# gsm2.net
KiCad netlist of a schematic drawn in Altium Designer
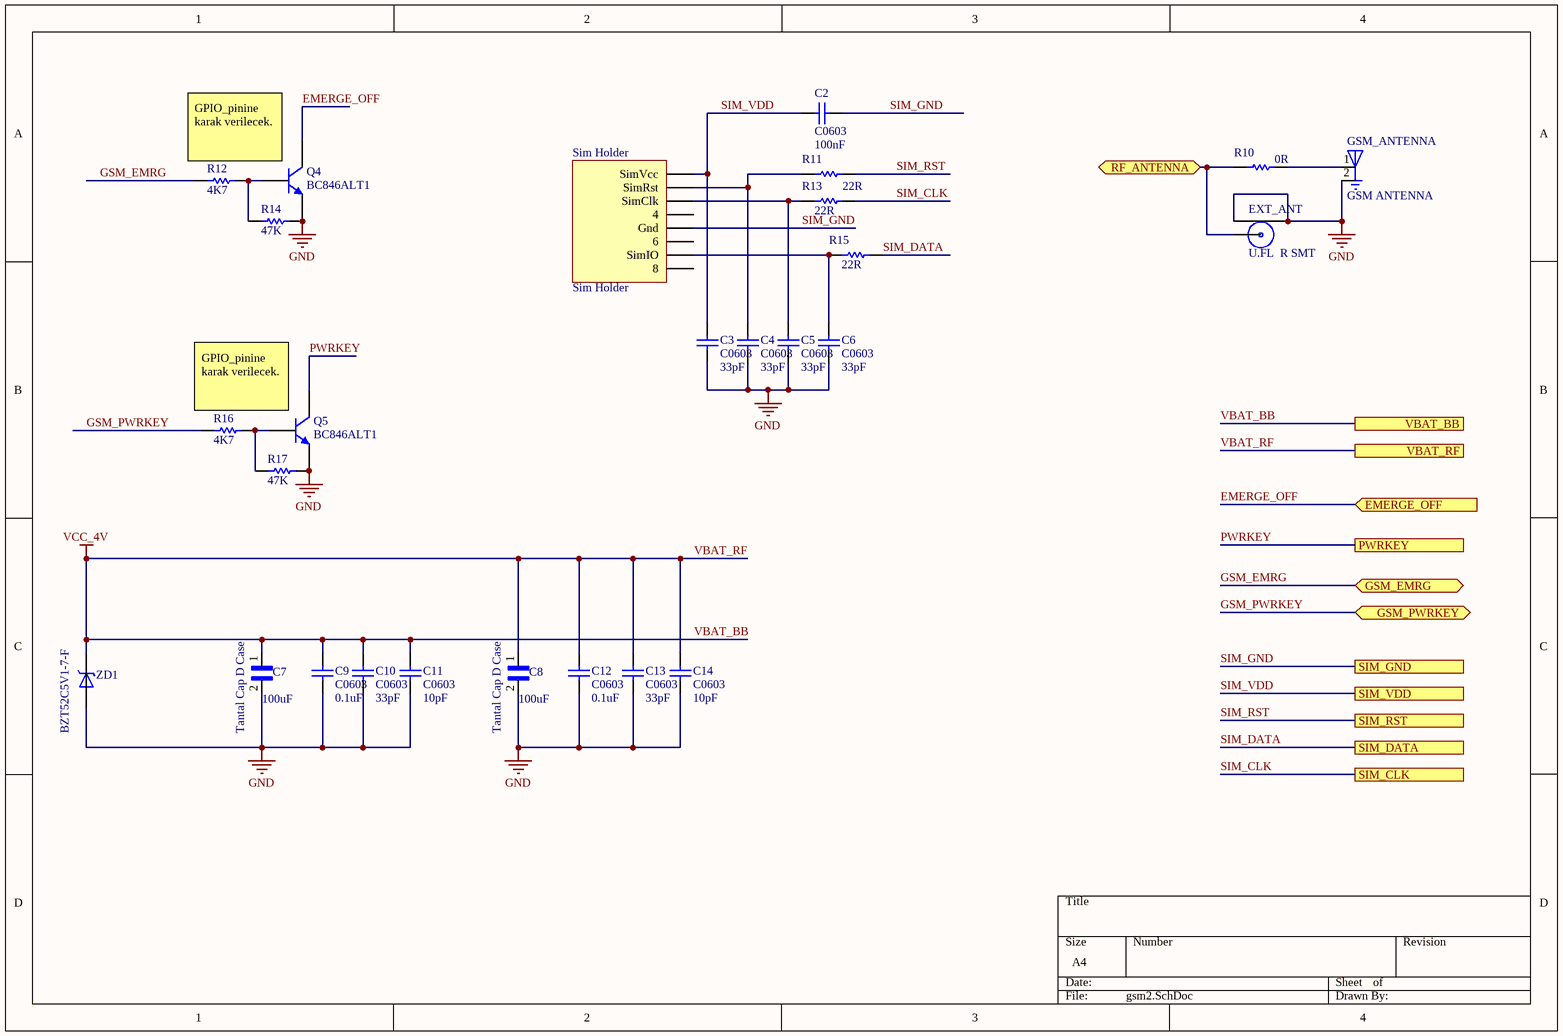
[diagram p0: gsm2.SchDoc]

(export (version "E")
  (design (tool "Eeschema 10.0.6"))
  (components
    (comp (ref "C2")
      (value "C0603")
      (footprint "C0603")
      (description "Ceramic Chip Capacitor - Standard")
      (fields (field (name "ALTIUM_VALUE") "100nF") (field (name "PUBLISHER") "Altium Limited"))
      (libsource (lib "haberlesme") (part "C0603"))
    )
    (comp (ref "C3")
      (value "C0603")
      (footprint "C0603")
      (description "Ceramic Chip Capacitor - Standard")
      (fields (field (name "ALTIUM_VALUE") "33pF") (field (name "PUBLISHER") "Altium Limited"))
      (libsource (lib "haberlesme") (part "C0603"))
    )
    (comp (ref "C4")
      (value "C0603")
      (footprint "C0603")
      (description "Ceramic Chip Capacitor - Standard")
      (fields (field (name "ALTIUM_VALUE") "33pF") (field (name "PUBLISHER") "Altium Limited"))
      (libsource (lib "haberlesme") (part "C0603"))
    )
    (comp (ref "C5")
      (value "C0603")
      (footprint "C0603")
      (description "Ceramic Chip Capacitor - Standard")
      (fields (field (name "ALTIUM_VALUE") "33pF") (field (name "PUBLISHER") "Altium Limited"))
      (libsource (lib "haberlesme") (part "C0603"))
    )
    (comp (ref "C6")
      (value "C0603")
      (footprint "C0603")
      (description "Ceramic Chip Capacitor - Standard")
      (fields (field (name "ALTIUM_VALUE") "33pF") (field (name "PUBLISHER") "Altium Limited"))
      (libsource (lib "haberlesme") (part "C0603"))
    )
    (comp (ref "C7")
      (value "Tantal Cap D Case")
      (footprint "Tantal Cap D Case")
      (fields (field (name "ALTIUM_VALUE") "100uF"))
      (libsource (lib "haberlesme") (part "Tantal Cap D Case"))
    )
    (comp (ref "C8")
      (value "Tantal Cap D Case")
      (footprint "Tantal Cap D Case")
      (fields (field (name "ALTIUM_VALUE") "100uF"))
      (libsource (lib "haberlesme") (part "Tantal Cap D Case"))
    )
    (comp (ref "C9")
      (value "C0603")
      (footprint "C0603")
      (description "Ceramic Chip Capacitor - Standard")
      (fields (field (name "ALTIUM_VALUE") "0.1uF") (field (name "PUBLISHER") "Altium Limited"))
      (libsource (lib "haberlesme") (part "C0603"))
    )
    (comp (ref "C10")
      (value "C0603")
      (footprint "C0603")
      (description "Ceramic Chip Capacitor - Standard")
      (fields (field (name "ALTIUM_VALUE") "33pF") (field (name "PUBLISHER") "Altium Limited"))
      (libsource (lib "haberlesme") (part "C0603"))
    )
    (comp (ref "C11")
      (value "C0603")
      (footprint "C0603")
      (description "Ceramic Chip Capacitor - Standard")
      (fields (field (name "ALTIUM_VALUE") "10pF") (field (name "PUBLISHER") "Altium Limited"))
      (libsource (lib "haberlesme") (part "C0603"))
    )
    (comp (ref "C12")
      (value "C0603")
      (footprint "C0603")
      (description "Ceramic Chip Capacitor - Standard")
      (fields (field (name "ALTIUM_VALUE") "0.1uF") (field (name "PUBLISHER") "Altium Limited"))
      (libsource (lib "haberlesme") (part "C0603"))
    )
    (comp (ref "C13")
      (value "C0603")
      (footprint "C0603")
      (description "Ceramic Chip Capacitor - Standard")
      (fields (field (name "ALTIUM_VALUE") "33pF") (field (name "PUBLISHER") "Altium Limited"))
      (libsource (lib "haberlesme") (part "C0603"))
    )
    (comp (ref "C14")
      (value "C0603")
      (footprint "C0603")
      (description "Ceramic Chip Capacitor - Standard")
      (fields (field (name "ALTIUM_VALUE") "10pF") (field (name "PUBLISHER") "Altium Limited"))
      (libsource (lib "haberlesme") (part "C0603"))
    )
    (comp (ref "EXT_ANT")
      (value "U.FL  R SMT")
      (footprint "U.FL  R SMT")
      (libsource (lib "haberlesme") (part "U.FL  R SMT"))
    )
    (comp (ref "GSM_ANTENNA")
      (value "GSM ANTENNA")
      (footprint "GSM ANTENNA")
      (libsource (lib "haberlesme") (part "GSM ANTENNA"))
    )
    (comp (ref "Q4")
      (value "BC846ALT1")
      (footprint "BC846")
      (description "General Purpose Transistor NPN Silicon")
      (fields (field (name "PUBLISHER") "Altium Limited"))
      (libsource (lib "Motorola Discrete BJT") (part "BC846ALT1"))
    )
    (comp (ref "Q5")
      (value "BC846ALT1")
      (footprint "BC846")
      (description "General Purpose Transistor NPN Silicon")
      (fields (field (name "PUBLISHER") "Altium Limited"))
      (libsource (lib "Motorola Discrete BJT") (part "BC846ALT1"))
    )
    (comp (ref "R10")
      (value "0R")
      (footprint "Isbak:CC1608-0603")
      (description "Resistor")
      (fields
        (field (name "MANUFACTURER") "Generic Components")
        (field (name "Comment") "Res0603")
        (field (name "PUBLISHER") "Altium Limited")
      )
      (libsource (lib "Isbak") (part "Res0603"))
    )
    (comp (ref "R11")
      (value "22R")
      (footprint "Isbak:CC1608-0603")
      (description "Resistor")
      (fields
        (field (name "MANUFACTURER") "Generic Components")
        (field (name "Comment") "Res0603")
        (field (name "PUBLISHER") "Altium Limited")
      )
      (libsource (lib "Isbak") (part "Res0603"))
    )
    (comp (ref "R12")
      (value "4K7")
      (footprint "Isbak:CC1608-0603")
      (description "Resistor")
      (fields
        (field (name "MANUFACTURER") "Generic Components")
        (field (name "Comment") "Res0603")
        (field (name "PUBLISHER") "Altium Limited")
      )
      (libsource (lib "Isbak") (part "Res0603"))
    )
    (comp (ref "R13")
      (value "22R")
      (footprint "Isbak:CC1608-0603")
      (description "Resistor")
      (fields
        (field (name "MANUFACTURER") "Generic Components")
        (field (name "Comment") "Res0603")
        (field (name "PUBLISHER") "Altium Limited")
      )
      (libsource (lib "Isbak") (part "Res0603"))
    )
    (comp (ref "R14")
      (value "47K")
      (footprint "Isbak:CC1608-0603")
      (description "Resistor")
      (fields
        (field (name "MANUFACTURER") "Generic Components")
        (field (name "Comment") "Res0603")
        (field (name "PUBLISHER") "Altium Limited")
      )
      (libsource (lib "Isbak") (part "Res0603"))
    )
    (comp (ref "R15")
      (value "22R")
      (footprint "Isbak:CC1608-0603")
      (description "Resistor")
      (fields
        (field (name "MANUFACTURER") "Generic Components")
        (field (name "Comment") "Res0603")
        (field (name "PUBLISHER") "Altium Limited")
      )
      (libsource (lib "Isbak") (part "Res0603"))
    )
    (comp (ref "R16")
      (value "4K7")
      (footprint "Isbak:CC1608-0603")
      (description "Resistor")
      (fields
        (field (name "MANUFACTURER") "Generic Components")
        (field (name "Comment") "Res0603")
        (field (name "PUBLISHER") "Altium Limited")
      )
      (libsource (lib "Isbak") (part "Res0603"))
    )
    (comp (ref "R17")
      (value "47K")
      (footprint "Isbak:CC1608-0603")
      (description "Resistor")
      (fields
        (field (name "MANUFACTURER") "Generic Components")
        (field (name "Comment") "Res0603")
        (field (name "PUBLISHER") "Altium Limited")
      )
      (libsource (lib "Isbak") (part "Res0603"))
    )
    (comp (ref "Sim Holder")
      (value "Sim Holder")
      (footprint "SIM HOLDER")
      (libsource (lib "haberlesme") (part "Sim Holder"))
    )
    (comp (ref "ZD1")
      (value "BZT52C5V1-7-F")
      (footprint "BZT52C5V1")
      (libsource (lib "haberlesme") (part "BZT52C5V1-7-F"))
    )
  )
  (nets
    (net (code "1") (name "/EMERGE_OFF") (class "Default")
      (node (ref "Q4") (pin "3") (pinfunction "C_3") (pintype "passive"))
    )
    (net (code "2") (name "/GSM_EMRG") (class "Default")
      (node (ref "R12") (pin "1") (pinfunction "1_1") (pintype "passive"))
    )
    (net (code "3") (name "/GSM_PWRKEY") (class "Default")
      (node (ref "R16") (pin "1") (pinfunction "1_1") (pintype "passive"))
    )
    (net (code "4") (name "/PWRKEY") (class "Default")
      (node (ref "Q5") (pin "3") (pinfunction "C_3") (pintype "passive"))
    )
    (net (code "5") (name "/RF_ANTENNA") (class "Default")
      (node (ref "EXT_ANT") (pin "P$1") (pinfunction "P$1_P$1") (pintype "passive"))
      (node (ref "R10") (pin "1") (pinfunction "1_1") (pintype "passive"))
    )
    (net (code "6") (name "/SIM_CLK") (class "Default")
      (node (ref "R13") (pin "2") (pinfunction "2_2") (pintype "passive"))
    )
    (net (code "7") (name "/SIM_DATA") (class "Default")
      (node (ref "R15") (pin "2") (pinfunction "2_2") (pintype "passive"))
    )
    (net (code "8") (name "/SIM_GND") (class "Default")
      (node (ref "C2") (pin "2") (pinfunction "2_2") (pintype "passive"))
      (node (ref "Sim Holder") (pin "5") (pinfunction "Gnd_5") (pintype "passive"))
    )
    (net (code "9") (name "/SIM_RST") (class "Default")
      (node (ref "R11") (pin "2") (pinfunction "2_2") (pintype "passive"))
    )
    (net (code "10") (name "/SIM_VDD") (class "Default")
      (node (ref "C2") (pin "1") (pinfunction "1_1") (pintype "passive"))
      (node (ref "C3") (pin "2") (pinfunction "2_2") (pintype "passive"))
      (node (ref "Sim Holder") (pin "1") (pinfunction "SimVcc_1") (pintype "passive"))
    )
    (net (code "11") (name "GND") (class "Default")
      (node (ref "C10") (pin "1") (pinfunction "1_1") (pintype "passive"))
      (node (ref "C11") (pin "1") (pinfunction "1_1") (pintype "passive"))
      (node (ref "C12") (pin "1") (pinfunction "1_1") (pintype "passive"))
      (node (ref "C13") (pin "1") (pinfunction "1_1") (pintype "passive"))
      (node (ref "C14") (pin "1") (pinfunction "1_1") (pintype "passive"))
      (node (ref "C3") (pin "1") (pinfunction "1_1") (pintype "passive"))
      (node (ref "C4") (pin "1") (pinfunction "1_1") (pintype "passive"))
      (node (ref "C5") (pin "1") (pinfunction "1_1") (pintype "passive"))
      (node (ref "C6") (pin "1") (pinfunction "1_1") (pintype "passive"))
      (node (ref "C7") (pin "2") (pinfunction "2_2") (pintype "passive"))
      (node (ref "C8") (pin "2") (pinfunction "2_2") (pintype "passive"))
      (node (ref "C9") (pin "1") (pinfunction "1_1") (pintype "passive"))
      (node (ref "EXT_ANT") (pin "P$2") (pinfunction "P$2_P$2") (pintype "power_in"))
      (node (ref "EXT_ANT") (pin "P$3") (pinfunction "P$3_P$3") (pintype "power_in"))
      (node (ref "GSM_ANTENNA") (pin "2") (pinfunction "GND_2") (pintype "power_in"))
      (node (ref "Q4") (pin "2") (pinfunction "E_2") (pintype "passive"))
      (node (ref "Q5") (pin "2") (pinfunction "E_2") (pintype "passive"))
      (node (ref "R14") (pin "2") (pinfunction "2_2") (pintype "passive"))
      (node (ref "R17") (pin "2") (pinfunction "2_2") (pintype "passive"))
      (node (ref "ZD1") (pin "A") (pinfunction "A_A") (pintype "passive"))
    )
    (net (code "12") (name "Net-(GSM_ANTENNA-FEEDING)") (class "Default")
      (node (ref "GSM_ANTENNA") (pin "1") (pinfunction "FEEDING_1") (pintype "passive"))
      (node (ref "R10") (pin "2") (pinfunction "2_2") (pintype "passive"))
    )
    (net (code "13") (name "Net-(Q4-B)") (class "Default")
      (node (ref "Q4") (pin "1") (pinfunction "B_1") (pintype "passive"))
      (node (ref "R12") (pin "2") (pinfunction "2_2") (pintype "passive"))
      (node (ref "R14") (pin "1") (pinfunction "1_1") (pintype "passive"))
    )
    (net (code "14") (name "Net-(Q5-B)") (class "Default")
      (node (ref "Q5") (pin "1") (pinfunction "B_1") (pintype "passive"))
      (node (ref "R16") (pin "2") (pinfunction "2_2") (pintype "passive"))
      (node (ref "R17") (pin "1") (pinfunction "1_1") (pintype "passive"))
    )
    (net (code "15") (name "Net-(Sim Holder-SimClk)") (class "Default")
      (node (ref "C5") (pin "2") (pinfunction "2_2") (pintype "passive"))
      (node (ref "R13") (pin "1") (pinfunction "1_1") (pintype "passive"))
      (node (ref "Sim Holder") (pin "3") (pinfunction "SimClk_3") (pintype "passive"))
    )
    (net (code "16") (name "Net-(Sim Holder-SimIO)") (class "Default")
      (node (ref "C6") (pin "2") (pinfunction "2_2") (pintype "passive"))
      (node (ref "R15") (pin "1") (pinfunction "1_1") (pintype "passive"))
      (node (ref "Sim Holder") (pin "7") (pinfunction "SimIO_7") (pintype "passive"))
    )
    (net (code "17") (name "Net-(Sim Holder-SimRst)") (class "Default")
      (node (ref "C4") (pin "2") (pinfunction "2_2") (pintype "passive"))
      (node (ref "R11") (pin "1") (pinfunction "1_1") (pintype "passive"))
      (node (ref "Sim Holder") (pin "2") (pinfunction "SimRst_2") (pintype "passive"))
    )
    (net (code "18") (name "VCC_4V") (class "Default")
      (node (ref "C10") (pin "2") (pinfunction "2_2") (pintype "passive"))
      (node (ref "C11") (pin "2") (pinfunction "2_2") (pintype "passive"))
      (node (ref "C12") (pin "2") (pinfunction "2_2") (pintype "passive"))
      (node (ref "C13") (pin "2") (pinfunction "2_2") (pintype "passive"))
      (node (ref "C14") (pin "2") (pinfunction "2_2") (pintype "passive"))
      (node (ref "C7") (pin "1") (pinfunction "1_1") (pintype "passive"))
      (node (ref "C8") (pin "1") (pinfunction "1_1") (pintype "passive"))
      (node (ref "C9") (pin "2") (pinfunction "2_2") (pintype "passive"))
      (node (ref "ZD1") (pin "C") (pinfunction "C_C") (pintype "passive"))
    )
    (net (code "19") (name "unconnected-(Sim Holder-Pad4)") (class "Default")
      (node (ref "Sim Holder") (pin "4") (pinfunction "4_4") (pintype "passive"))
    )
    (net (code "20") (name "unconnected-(Sim Holder-Pad6)") (class "Default")
      (node (ref "Sim Holder") (pin "6") (pinfunction "6_6") (pintype "passive"))
    )
    (net (code "21") (name "unconnected-(Sim Holder-Pad8)") (class "Default")
      (node (ref "Sim Holder") (pin "8") (pinfunction "8_8") (pintype "passive"))
    )
  )
)
